# schematic_1.net
KiCad netlist of a schematic drawn in EAGLE
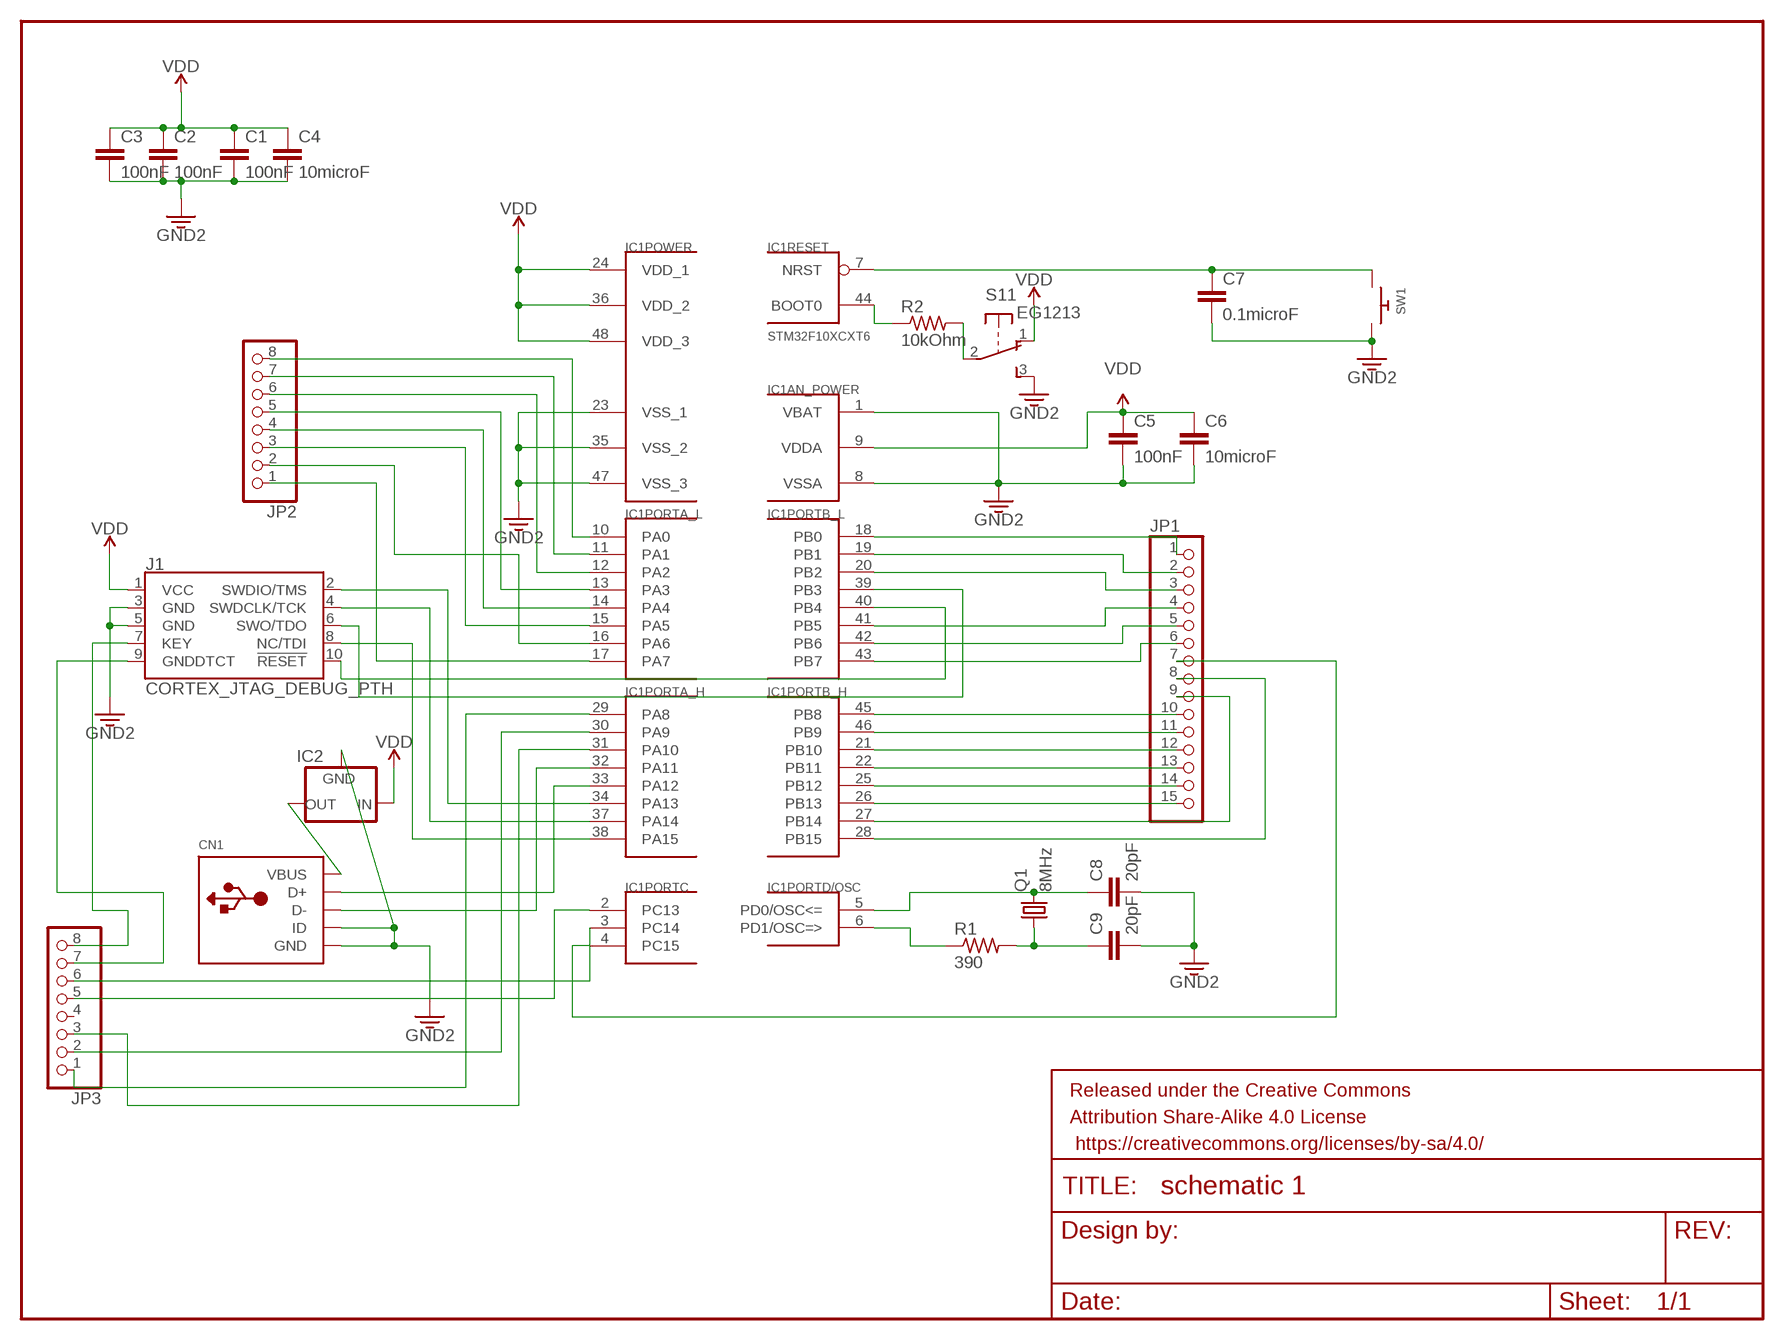
[diagram p0: schematic, sheet 1]

(export (version "E")
  (design (tool "Eeschema 10.0.6"))
  (components
    (comp (ref "C1")
      (value "100nF")
      (footprint "eagle-import:C2.5-3")
      (libsource (lib "eagle-import") (part "C2,5-3"))
    )
    (comp (ref "C2")
      (value "100nF")
      (footprint "eagle-import:C2.5-3")
      (libsource (lib "eagle-import") (part "C2,5-3"))
    )
    (comp (ref "C3")
      (value "100nF")
      (footprint "eagle-import:C2.5-3")
      (libsource (lib "eagle-import") (part "C2,5-3"))
    )
    (comp (ref "C4")
      (value "10microF")
      (footprint "eagle-import:C2.5-3")
      (libsource (lib "eagle-import") (part "C2,5-3"))
    )
    (comp (ref "C5")
      (value "100nF")
      (footprint "eagle-import:C2.5-3")
      (libsource (lib "eagle-import") (part "C2,5-3"))
    )
    (comp (ref "C6")
      (value "10microF")
      (footprint "eagle-import:C2.5-3")
      (libsource (lib "eagle-import") (part "C2,5-3"))
    )
    (comp (ref "C7")
      (value "0.1microF")
      (footprint "eagle-import:C2.5-3")
      (libsource (lib "eagle-import") (part "C2,5-3"))
    )
    (comp (ref "C8")
      (value "20pF")
      (footprint "eagle-import:C2.5-3")
      (libsource (lib "eagle-import") (part "C2,5-3"))
    )
    (comp (ref "C9")
      (value "20pF")
      (footprint "eagle-import:C2.5-3")
      (libsource (lib "eagle-import") (part "C2,5-3"))
    )
    (comp (ref "CN1")
      (value "USBMINIB")
      (footprint "eagle-import:USB-MINIB")
      (libsource (lib "eagle-import") (part "USBMINIB"))
    )
    (comp (ref "FRAME1")
      (value "FRAME-LETTER")
      (footprint "eagle-import:CREATIVE_COMMONS")
      (libsource (lib "eagle-import") (part "FRAME-LETTER"))
    )
    (comp (ref "IC1")
      (value "STM32F10XCXT6")
      (footprint "eagle-import:TQFP48")
      (libsource (lib "eagle-import") (part "STM32F10XCXT6"))
    )
    (comp (ref "IC2")
      (value "MCP1700INLINE")
      (footprint "eagle-import:TO92-INLINE")
      (libsource (lib "eagle-import") (part "MCP1700INLINE"))
    )
    (comp (ref "J1")
      (value "CORTEX_JTAG_DEBUG_PTH")
      (footprint "eagle-import:2X5-PTH-1.27MM")
      (libsource (lib "eagle-import") (part "CORTEX_JTAG_DEBUG_PTH"))
    )
    (comp (ref "JP1")
      (value "PINHD-1X15-CB")
      (footprint "eagle-import:1X15-CB")
      (libsource (lib "eagle-import") (part "PINHD-1X15-CB"))
    )
    (comp (ref "JP2")
      (value "PINHD-1X8-3.5MM")
      (footprint "eagle-import:1X08-3.5MM")
      (libsource (lib "eagle-import") (part "PINHD-1X8-3.5MM"))
    )
    (comp (ref "JP3")
      (value "PINHD-1X8-3.5MM")
      (footprint "eagle-import:1X08-3.5MM")
      (libsource (lib "eagle-import") (part "PINHD-1X8-3.5MM"))
    )
    (comp (ref "Q1")
      (value "8MHz")
      (footprint "eagle-import:86SMX")
      (libsource (lib "eagle-import") (part "CRYSTAL68SMX"))
    )
    (comp (ref "R1")
      (value "390")
      (footprint "eagle-import:0805-THM")
      (libsource (lib "eagle-import") (part "FLIPFLOP-RES"))
    )
    (comp (ref "R2")
      (value "10kOhm")
      (footprint "eagle-import:0805-THM")
      (libsource (lib "eagle-import") (part "FLIPFLOP-RES"))
    )
    (comp (ref "S1")
      (value "EG1213")
      (footprint "eagle-import:EG1213")
      (libsource (lib "eagle-import") (part "EG1213"))
    )
    (comp (ref "SW1")
      (value "SWITCH_PUSHBUTTONEVQ-PE")
      (footprint "eagle-import:TACT_PANA-EVQ")
      (libsource (lib "eagle-import") (part "SWITCH_PUSHBUTTONEVQ-PE"))
    )
  )
  (nets
    (net (code "1") (name "GND2") (class "Default")
      (node (ref "C1") (pin "2") (pinfunction "2_2") (pintype "passive"))
      (node (ref "C2") (pin "2") (pinfunction "2_2") (pintype "passive"))
      (node (ref "C3") (pin "2") (pinfunction "2_2") (pintype "passive"))
      (node (ref "C4") (pin "2") (pinfunction "2_2") (pintype "passive"))
      (node (ref "C5") (pin "2") (pinfunction "2_2") (pintype "passive"))
      (node (ref "C6") (pin "2") (pinfunction "2_2") (pintype "passive"))
      (node (ref "C7") (pin "2") (pinfunction "2_2") (pintype "passive"))
      (node (ref "C8") (pin "2") (pinfunction "2_2") (pintype "passive"))
      (node (ref "C9") (pin "2") (pinfunction "2_2") (pintype "passive"))
      (node (ref "CN1") (pin "GND") (pinfunction "GND_GND") (pintype "power_in"))
      (node (ref "CN1") (pin "ID") (pinfunction "ID_ID") (pintype "bidirectional"))
      (node (ref "IC1") (pin "1") (pinfunction "VBAT_1") (pintype "power_in"))
      (node (ref "IC1") (pin "23") (pinfunction "VSS_1_23") (pintype "power_in"))
      (node (ref "IC1") (pin "35") (pinfunction "VSS_2_35") (pintype "power_in"))
      (node (ref "IC1") (pin "47") (pinfunction "VSS_3_47") (pintype "power_in"))
      (node (ref "IC1") (pin "8") (pinfunction "VSSA_8") (pintype "power_in"))
      (node (ref "IC2") (pin "1") (pinfunction "GND_1") (pintype "input"))
      (node (ref "J1") (pin "3") (pinfunction "GND_3") (pintype "bidirectional"))
      (node (ref "J1") (pin "5") (pinfunction "GND_5") (pintype "bidirectional"))
      (node (ref "S1") (pin "3") (pinfunction "S_3") (pintype "passive"))
      (node (ref "SW1") (pin "P$2") (pinfunction "P$2_P$2") (pintype "passive"))
    )
    (net (code "2") (name "Net-(C9-Pad1)") (class "Default")
      (node (ref "C9") (pin "1") (pinfunction "1_1") (pintype "passive"))
      (node (ref "Q1") (pin "1") (pinfunction "1_1") (pintype "passive"))
      (node (ref "R1") (pin "2") (pinfunction "2_2") (pintype "passive"))
    )
    (net (code "3") (name "Net-(IC1B-PA8)") (class "Default")
      (node (ref "IC1") (pin "29") (pinfunction "PA8_29") (pintype "bidirectional"))
      (node (ref "JP3") (pin "1") (pinfunction "1_1") (pintype "passive"))
    )
    (net (code "4") (name "Net-(IC1B-PA9)") (class "Default")
      (node (ref "IC1") (pin "30") (pinfunction "PA9_30") (pintype "bidirectional"))
      (node (ref "JP3") (pin "2") (pinfunction "2_2") (pintype "passive"))
    )
    (net (code "5") (name "Net-(IC1B-PA10)") (class "Default")
      (node (ref "IC1") (pin "31") (pinfunction "PA10_31") (pintype "bidirectional"))
      (node (ref "JP3") (pin "3") (pinfunction "3_3") (pintype "passive"))
    )
    (net (code "6") (name "Net-(IC1B-PA11)") (class "Default")
      (node (ref "CN1") (pin "D-") (pinfunction "D-_D-") (pintype "bidirectional"))
      (node (ref "IC1") (pin "32") (pinfunction "PA11_32") (pintype "bidirectional"))
    )
    (net (code "7") (name "Net-(IC1B-PA12)") (class "Default")
      (node (ref "CN1") (pin "D+") (pinfunction "D+_D+") (pintype "bidirectional"))
      (node (ref "IC1") (pin "33") (pinfunction "PA12_33") (pintype "bidirectional"))
    )
    (net (code "8") (name "Net-(IC1B-PA13)") (class "Default")
      (node (ref "IC1") (pin "34") (pinfunction "PA13_34") (pintype "bidirectional"))
      (node (ref "J1") (pin "2") (pinfunction "SWDIO/TMS_2") (pintype "bidirectional"))
    )
    (net (code "9") (name "Net-(IC1B-PA14)") (class "Default")
      (node (ref "IC1") (pin "37") (pinfunction "PA14_37") (pintype "bidirectional"))
      (node (ref "J1") (pin "4") (pinfunction "SWDCLK/TCK_4") (pintype "bidirectional"))
    )
    (net (code "10") (name "Net-(IC1B-PA15)") (class "Default")
      (node (ref "IC1") (pin "38") (pinfunction "PA15_38") (pintype "bidirectional"))
      (node (ref "J1") (pin "8") (pinfunction "NC/TDI_8") (pintype "bidirectional"))
    )
    (net (code "11") (name "Net-(IC1C-PA0)") (class "Default")
      (node (ref "IC1") (pin "10") (pinfunction "PA0_10") (pintype "bidirectional"))
      (node (ref "JP2") (pin "8") (pinfunction "8_8") (pintype "passive"))
    )
    (net (code "12") (name "Net-(IC1C-PA1)") (class "Default")
      (node (ref "IC1") (pin "11") (pinfunction "PA1_11") (pintype "bidirectional"))
      (node (ref "JP2") (pin "7") (pinfunction "7_7") (pintype "passive"))
    )
    (net (code "13") (name "Net-(IC1C-PA2)") (class "Default")
      (node (ref "IC1") (pin "12") (pinfunction "PA2_12") (pintype "bidirectional"))
      (node (ref "JP2") (pin "6") (pinfunction "6_6") (pintype "passive"))
    )
    (net (code "14") (name "Net-(IC1C-PA3)") (class "Default")
      (node (ref "IC1") (pin "13") (pinfunction "PA3_13") (pintype "bidirectional"))
      (node (ref "JP2") (pin "5") (pinfunction "5_5") (pintype "passive"))
    )
    (net (code "15") (name "Net-(IC1C-PA4)") (class "Default")
      (node (ref "IC1") (pin "14") (pinfunction "PA4_14") (pintype "bidirectional"))
      (node (ref "JP2") (pin "4") (pinfunction "4_4") (pintype "passive"))
    )
    (net (code "16") (name "Net-(IC1C-PA5)") (class "Default")
      (node (ref "IC1") (pin "15") (pinfunction "PA5_15") (pintype "bidirectional"))
      (node (ref "JP2") (pin "3") (pinfunction "3_3") (pintype "passive"))
    )
    (net (code "17") (name "Net-(IC1C-PA6)") (class "Default")
      (node (ref "IC1") (pin "16") (pinfunction "PA6_16") (pintype "bidirectional"))
      (node (ref "JP2") (pin "2") (pinfunction "2_2") (pintype "passive"))
    )
    (net (code "18") (name "Net-(IC1C-PA7)") (class "Default")
      (node (ref "IC1") (pin "17") (pinfunction "PA7_17") (pintype "bidirectional"))
      (node (ref "JP2") (pin "1") (pinfunction "1_1") (pintype "passive"))
    )
    (net (code "19") (name "Net-(IC1D-PB8)") (class "Default")
      (node (ref "IC1") (pin "45") (pinfunction "PB8_45") (pintype "bidirectional"))
      (node (ref "JP1") (pin "10") (pinfunction "10_10") (pintype "passive"))
    )
    (net (code "20") (name "Net-(IC1D-PB9)") (class "Default")
      (node (ref "IC1") (pin "46") (pinfunction "PB9_46") (pintype "bidirectional"))
      (node (ref "JP1") (pin "11") (pinfunction "11_11") (pintype "passive"))
    )
    (net (code "21") (name "Net-(IC1D-PB10)") (class "Default")
      (node (ref "IC1") (pin "21") (pinfunction "PB10_21") (pintype "bidirectional"))
      (node (ref "JP1") (pin "12") (pinfunction "12_12") (pintype "passive"))
    )
    (net (code "22") (name "Net-(IC1D-PB11)") (class "Default")
      (node (ref "IC1") (pin "22") (pinfunction "PB11_22") (pintype "bidirectional"))
      (node (ref "JP1") (pin "13") (pinfunction "13_13") (pintype "passive"))
    )
    (net (code "23") (name "Net-(IC1D-PB12)") (class "Default")
      (node (ref "IC1") (pin "25") (pinfunction "PB12_25") (pintype "bidirectional"))
      (node (ref "JP1") (pin "14") (pinfunction "14_14") (pintype "passive"))
    )
    (net (code "24") (name "Net-(IC1D-PB13)") (class "Default")
      (node (ref "IC1") (pin "26") (pinfunction "PB13_26") (pintype "bidirectional"))
      (node (ref "JP1") (pin "15") (pinfunction "15_15") (pintype "passive"))
    )
    (net (code "25") (name "Net-(IC1D-PB14)") (class "Default")
      (node (ref "IC1") (pin "27") (pinfunction "PB14_27") (pintype "bidirectional"))
      (node (ref "JP1") (pin "9") (pinfunction "9_9") (pintype "passive"))
    )
    (net (code "26") (name "Net-(IC1D-PB15)") (class "Default")
      (node (ref "IC1") (pin "28") (pinfunction "PB15_28") (pintype "bidirectional"))
      (node (ref "JP1") (pin "8") (pinfunction "8_8") (pintype "passive"))
    )
    (net (code "27") (name "Net-(IC1E-PB0)") (class "Default")
      (node (ref "IC1") (pin "18") (pinfunction "PB0_18") (pintype "bidirectional"))
      (node (ref "JP1") (pin "1") (pinfunction "1_1") (pintype "passive"))
    )
    (net (code "28") (name "Net-(IC1E-PB1)") (class "Default")
      (node (ref "IC1") (pin "19") (pinfunction "PB1_19") (pintype "bidirectional"))
      (node (ref "JP1") (pin "2") (pinfunction "2_2") (pintype "passive"))
    )
    (net (code "29") (name "Net-(IC1E-PB2)") (class "Default")
      (node (ref "IC1") (pin "20") (pinfunction "PB2_20") (pintype "bidirectional"))
      (node (ref "JP1") (pin "3") (pinfunction "3_3") (pintype "passive"))
    )
    (net (code "30") (name "Net-(IC1E-PB3)") (class "Default")
      (node (ref "IC1") (pin "39") (pinfunction "PB3_39") (pintype "bidirectional"))
      (node (ref "J1") (pin "6") (pinfunction "SWO/TDO_6") (pintype "bidirectional"))
    )
    (net (code "31") (name "Net-(IC1E-PB4)") (class "Default")
      (node (ref "IC1") (pin "40") (pinfunction "PB4_40") (pintype "bidirectional"))
      (node (ref "J1") (pin "10") (pinfunction "~{RESET}_10") (pintype "bidirectional"))
    )
    (net (code "32") (name "Net-(IC1E-PB5)") (class "Default")
      (node (ref "IC1") (pin "41") (pinfunction "PB5_41") (pintype "bidirectional"))
      (node (ref "JP1") (pin "4") (pinfunction "4_4") (pintype "passive"))
    )
    (net (code "33") (name "Net-(IC1E-PB6)") (class "Default")
      (node (ref "IC1") (pin "42") (pinfunction "PB6_42") (pintype "bidirectional"))
      (node (ref "JP1") (pin "5") (pinfunction "5_5") (pintype "passive"))
    )
    (net (code "34") (name "Net-(IC1E-PB7)") (class "Default")
      (node (ref "IC1") (pin "43") (pinfunction "PB7_43") (pintype "bidirectional"))
      (node (ref "JP1") (pin "6") (pinfunction "6_6") (pintype "passive"))
    )
    (net (code "35") (name "Net-(IC1F-PC13)") (class "Default")
      (node (ref "IC1") (pin "2") (pinfunction "PC13_2") (pintype "bidirectional"))
      (node (ref "JP3") (pin "5") (pinfunction "5_5") (pintype "passive"))
    )
    (net (code "36") (name "Net-(IC1F-PC14)") (class "Default")
      (node (ref "IC1") (pin "3") (pinfunction "PC14_3") (pintype "bidirectional"))
      (node (ref "JP3") (pin "6") (pinfunction "6_6") (pintype "passive"))
    )
    (net (code "37") (name "Net-(IC1F-PC15)") (class "Default")
      (node (ref "IC1") (pin "4") (pinfunction "PC15_4") (pintype "bidirectional"))
      (node (ref "JP1") (pin "7") (pinfunction "7_7") (pintype "passive"))
    )
    (net (code "38") (name "Net-(IC1G-PD0{slash}OSC<=)") (class "Default")
      (node (ref "C8") (pin "1") (pinfunction "1_1") (pintype "passive"))
      (node (ref "IC1") (pin "5") (pinfunction "PD0/OSC<=_5") (pintype "bidirectional"))
      (node (ref "Q1") (pin "4") (pinfunction "2_4") (pintype "passive"))
    )
    (net (code "39") (name "Net-(IC1G-PD1{slash}OSC=>)") (class "Default")
      (node (ref "IC1") (pin "6") (pinfunction "PD1/OSC=>_6") (pintype "bidirectional"))
      (node (ref "R1") (pin "1") (pinfunction "1_1") (pintype "passive"))
    )
    (net (code "40") (name "Net-(IC1I-BOOT0)") (class "Default")
      (node (ref "IC1") (pin "44") (pinfunction "BOOT0_44") (pintype "input"))
      (node (ref "R2") (pin "1") (pinfunction "1_1") (pintype "passive"))
    )
    (net (code "41") (name "Net-(IC1I-NRST)") (class "Default")
      (node (ref "C7") (pin "1") (pinfunction "1_1") (pintype "passive"))
      (node (ref "IC1") (pin "7") (pinfunction "NRST_7") (pintype "input"))
      (node (ref "SW1") (pin "P$1") (pinfunction "P$1_P$1") (pintype "passive"))
    )
    (net (code "42") (name "Net-(IC2-OUT)") (class "Default")
      (node (ref "CN1") (pin "VBUS") (pinfunction "VBUS_VBUS") (pintype "power_in"))
      (node (ref "IC2") (pin "3") (pinfunction "OUT_3") (pintype "passive"))
    )
    (net (code "43") (name "Net-(J1-GNDDTCT)") (class "Default")
      (node (ref "J1") (pin "9") (pinfunction "GNDDTCT_9") (pintype "bidirectional"))
      (node (ref "JP3") (pin "7") (pinfunction "7_7") (pintype "passive"))
    )
    (net (code "44") (name "Net-(J1-KEY)") (class "Default")
      (node (ref "J1") (pin "7") (pinfunction "KEY_7") (pintype "bidirectional"))
      (node (ref "JP3") (pin "8") (pinfunction "8_8") (pintype "passive"))
    )
    (net (code "45") (name "Net-(S1A-P)") (class "Default")
      (node (ref "R2") (pin "2") (pinfunction "2_2") (pintype "passive"))
      (node (ref "S1") (pin "2") (pinfunction "P_2") (pintype "passive"))
    )
    (net (code "46") (name "VDD") (class "Default")
      (node (ref "C1") (pin "1") (pinfunction "1_1") (pintype "passive"))
      (node (ref "C2") (pin "1") (pinfunction "1_1") (pintype "passive"))
      (node (ref "C3") (pin "1") (pinfunction "1_1") (pintype "passive"))
      (node (ref "C4") (pin "1") (pinfunction "1_1") (pintype "passive"))
      (node (ref "C5") (pin "1") (pinfunction "1_1") (pintype "passive"))
      (node (ref "C6") (pin "1") (pinfunction "1_1") (pintype "passive"))
      (node (ref "IC1") (pin "24") (pinfunction "VDD_1_24") (pintype "power_in"))
      (node (ref "IC1") (pin "36") (pinfunction "VDD_2_36") (pintype "power_in"))
      (node (ref "IC1") (pin "48") (pinfunction "VDD_3_48") (pintype "power_in"))
      (node (ref "IC1") (pin "9") (pinfunction "VDDA_9") (pintype "power_in"))
      (node (ref "IC2") (pin "2") (pinfunction "IN_2") (pintype "input"))
      (node (ref "J1") (pin "1") (pinfunction "VCC_1") (pintype "bidirectional"))
      (node (ref "S1") (pin "1") (pinfunction "O_1") (pintype "passive"))
    )
    (net (code "47") (name "unconnected-(JP3-Pad4)") (class "Default")
      (node (ref "JP3") (pin "4") (pinfunction "4_4") (pintype "passive"))
    )
  )
)
